# 2513_Replacement.net
KiCad netlist of a schematic drawn in EasyEDA
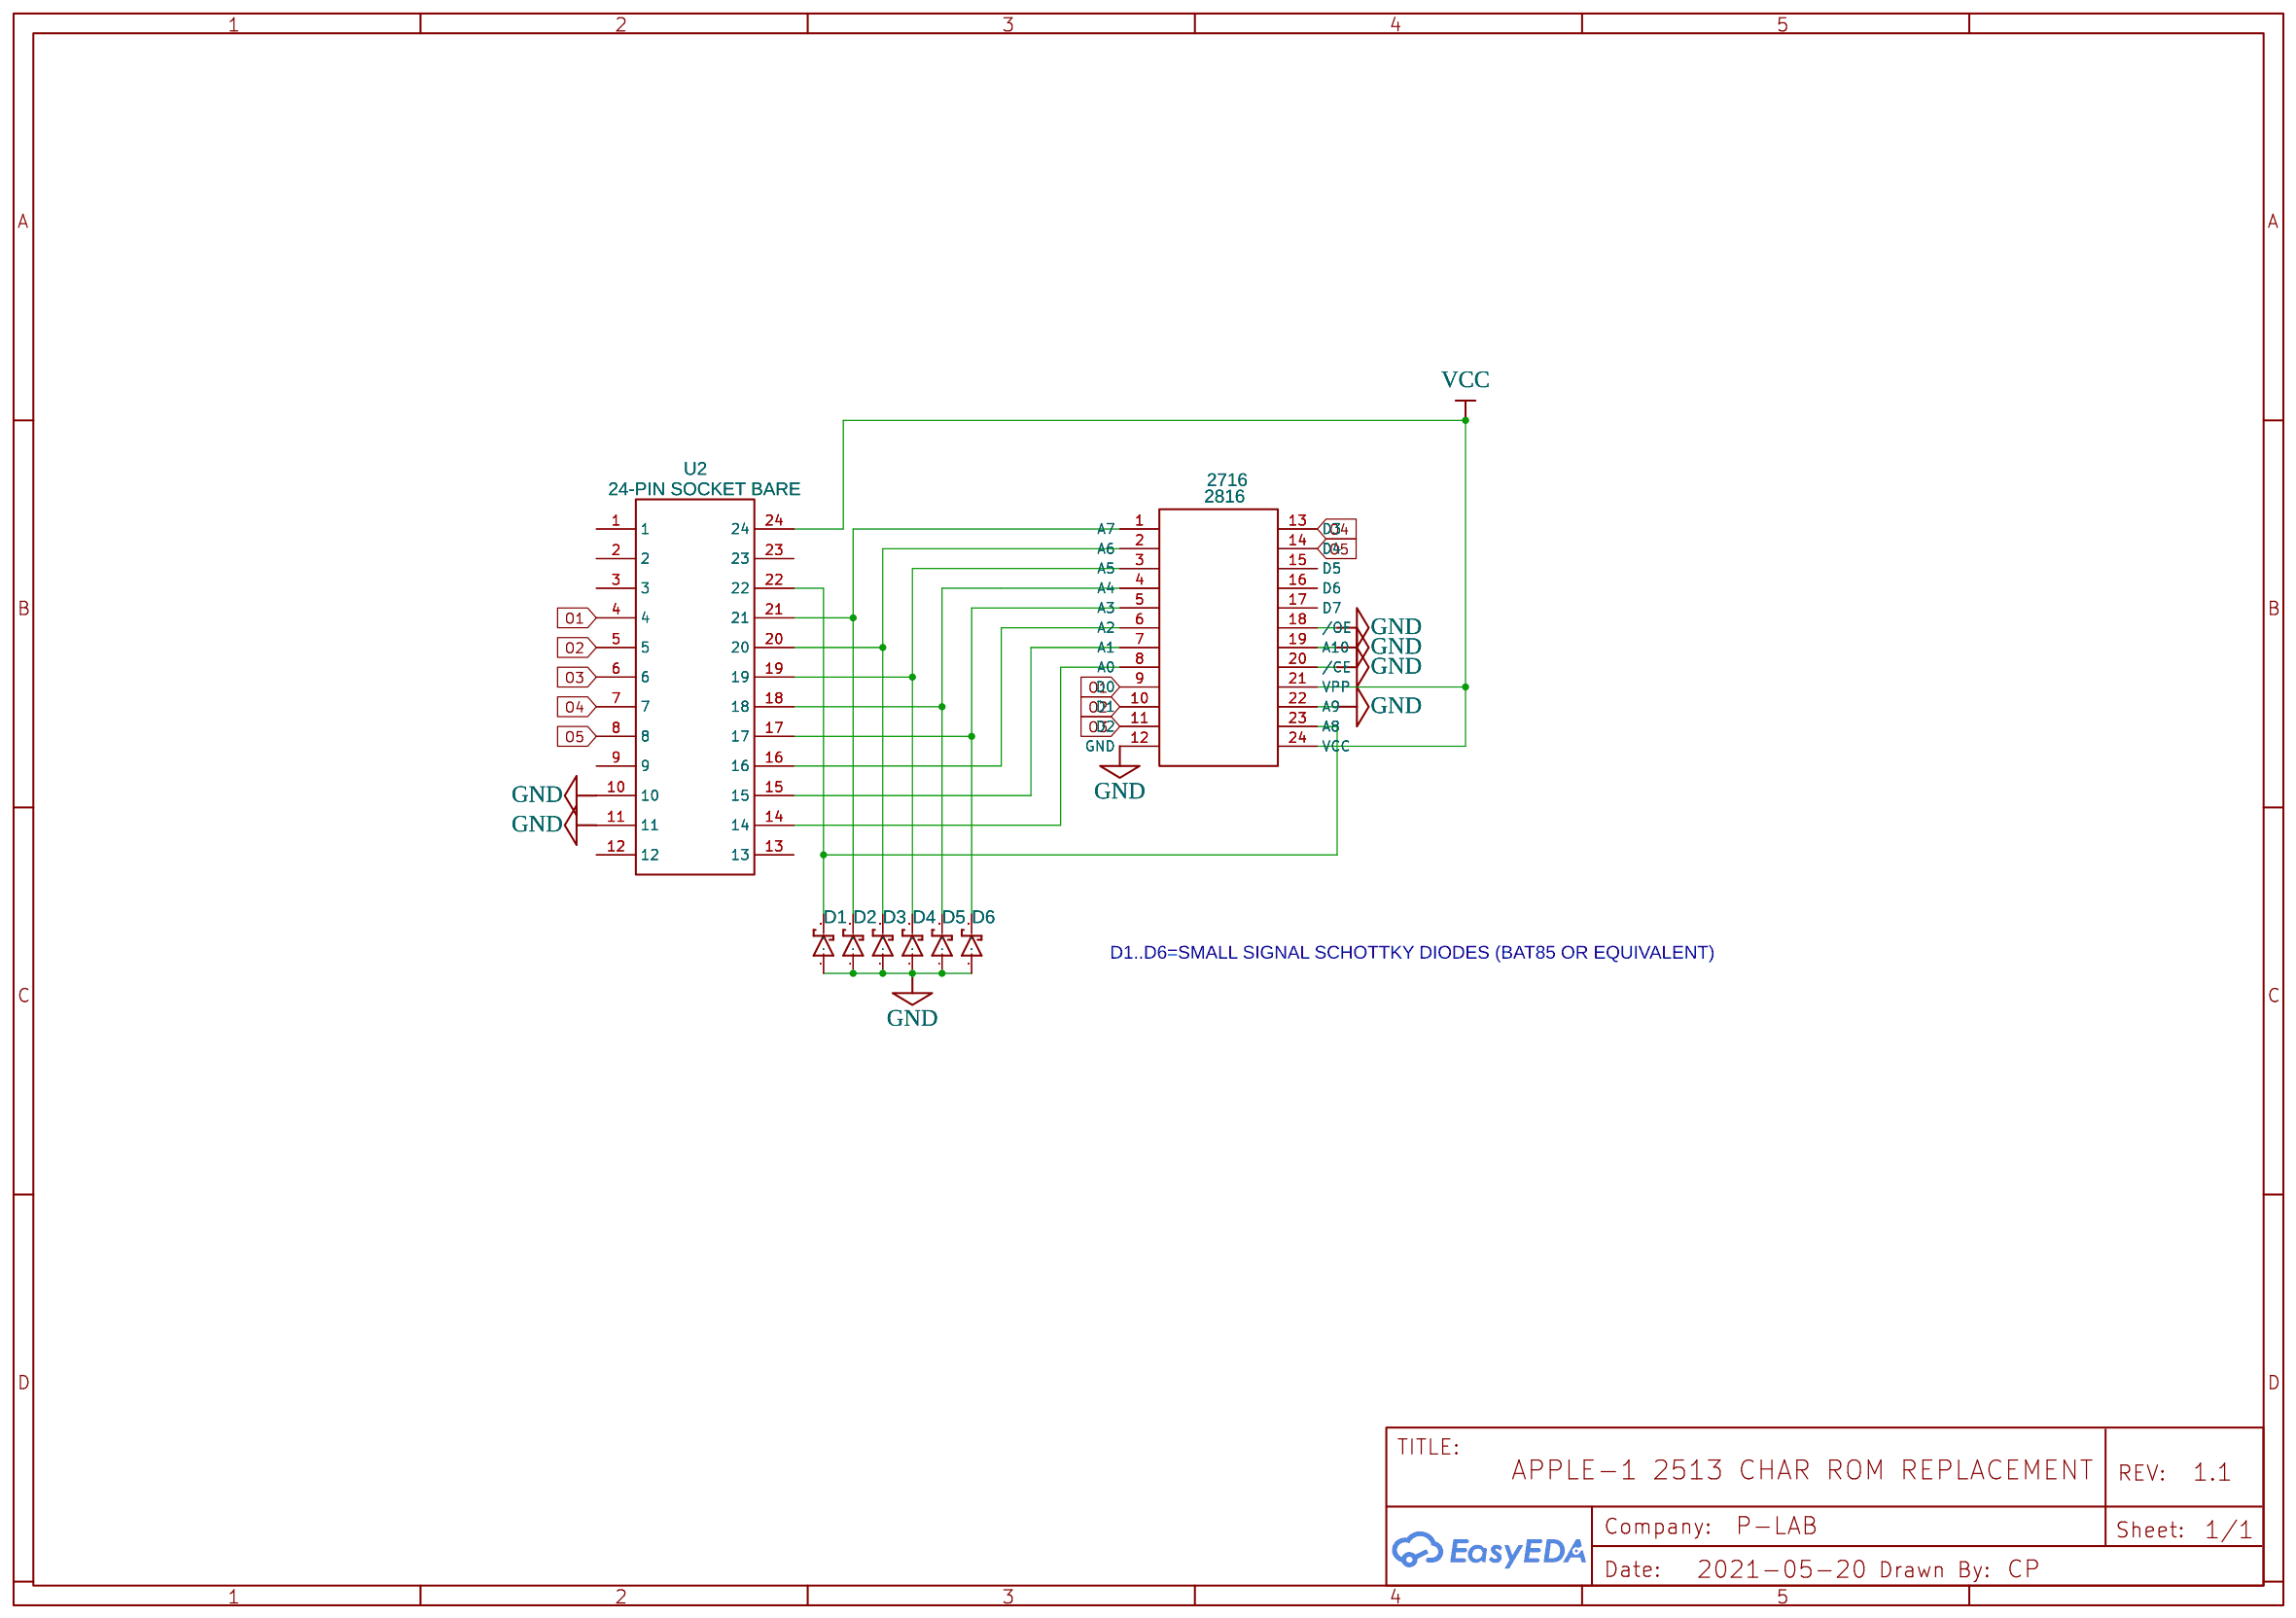
[diagram p0: schematic sheet]

(export (version "E")
  (design (tool "Eeschema 10.0.6"))
  (components
    (comp (ref "2716")
      (value "2816")
      (fields (field (name "BOM_Manufacturer Part") "27C16"))
      (libsource (lib "") (part "2716"))
    )
    (comp (ref "D1") (value "SCHOTTKY") (libsource (lib "") (part "SCHOTTKY")))
    (comp (ref "D2") (value "SCHOTTKY") (libsource (lib "") (part "SCHOTTKY")))
    (comp (ref "D3") (value "SCHOTTKY") (libsource (lib "") (part "SCHOTTKY")))
    (comp (ref "D4") (value "SCHOTTKY") (libsource (lib "") (part "SCHOTTKY")))
    (comp (ref "D5") (value "SCHOTTKY") (libsource (lib "") (part "SCHOTTKY")))
    (comp (ref "D6") (value "SCHOTTKY") (libsource (lib "") (part "SCHOTTKY")))
    (comp (ref "U2") (value "24-PIN SOCKET BARE") (libsource (lib "") (part "24-PIN SOCKET BARE")))
  )
  (nets
    (net (code "1") (name "GND") (class "Default")
      (node (ref "2716") (pin "12") (pinfunction "GND_12") (pintype "unspecified"))
      (node (ref "2716") (pin "18") (pinfunction "/OE_18") (pintype "unspecified"))
      (node (ref "2716") (pin "19") (pinfunction "A10_19") (pintype "unspecified"))
      (node (ref "2716") (pin "20") (pinfunction "/CE_20") (pintype "unspecified"))
      (node (ref "2716") (pin "22") (pinfunction "A9_22") (pintype "unspecified"))
      (node (ref "D1") (pin "A") (pinfunction "A_A") (pintype "bidirectional"))
      (node (ref "D2") (pin "A") (pinfunction "A_A") (pintype "bidirectional"))
      (node (ref "D3") (pin "A") (pinfunction "A_A") (pintype "bidirectional"))
      (node (ref "D4") (pin "A") (pinfunction "A_A") (pintype "bidirectional"))
      (node (ref "D5") (pin "A") (pinfunction "A_A") (pintype "bidirectional"))
      (node (ref "D6") (pin "A") (pinfunction "A_A") (pintype "bidirectional"))
      (node (ref "U2") (pin "10") (pinfunction "10_10") (pintype "unspecified"))
      (node (ref "U2") (pin "11") (pinfunction "11_11") (pintype "unspecified"))
    )
    (net (code "2") (name "Net-(2716-A0)") (class "Default")
      (node (ref "2716") (pin "8") (pinfunction "A0_8") (pintype "unspecified"))
      (node (ref "U2") (pin "14") (pinfunction "14_14") (pintype "unspecified"))
    )
    (net (code "3") (name "Net-(2716-A1)") (class "Default")
      (node (ref "2716") (pin "7") (pinfunction "A1_7") (pintype "unspecified"))
      (node (ref "U2") (pin "15") (pinfunction "15_15") (pintype "unspecified"))
    )
    (net (code "4") (name "Net-(2716-A2)") (class "Default")
      (node (ref "2716") (pin "6") (pinfunction "A2_6") (pintype "unspecified"))
      (node (ref "U2") (pin "16") (pinfunction "16_16") (pintype "unspecified"))
    )
    (net (code "5") (name "Net-(2716-A3)") (class "Default")
      (node (ref "2716") (pin "5") (pinfunction "A3_5") (pintype "unspecified"))
      (node (ref "D6") (pin "C") (pinfunction "C_C") (pintype "bidirectional"))
      (node (ref "U2") (pin "17") (pinfunction "17_17") (pintype "unspecified"))
    )
    (net (code "6") (name "Net-(2716-A4)") (class "Default")
      (node (ref "2716") (pin "4") (pinfunction "A4_4") (pintype "unspecified"))
      (node (ref "D5") (pin "C") (pinfunction "C_C") (pintype "bidirectional"))
      (node (ref "U2") (pin "18") (pinfunction "18_18") (pintype "bidirectional"))
    )
    (net (code "7") (name "Net-(2716-A5)") (class "Default")
      (node (ref "2716") (pin "3") (pinfunction "A5_3") (pintype "unspecified"))
      (node (ref "D4") (pin "C") (pinfunction "C_C") (pintype "bidirectional"))
      (node (ref "U2") (pin "19") (pinfunction "19_19") (pintype "bidirectional"))
    )
    (net (code "8") (name "Net-(2716-A6)") (class "Default")
      (node (ref "2716") (pin "2") (pinfunction "A6_2") (pintype "unspecified"))
      (node (ref "D3") (pin "C") (pinfunction "C_C") (pintype "bidirectional"))
      (node (ref "U2") (pin "20") (pinfunction "20_20") (pintype "bidirectional"))
    )
    (net (code "9") (name "Net-(2716-A7)") (class "Default")
      (node (ref "2716") (pin "1") (pinfunction "A7_1") (pintype "unspecified"))
      (node (ref "D2") (pin "C") (pinfunction "C_C") (pintype "bidirectional"))
      (node (ref "U2") (pin "21") (pinfunction "21_21") (pintype "bidirectional"))
    )
    (net (code "10") (name "Net-(2716-A8)") (class "Default")
      (node (ref "2716") (pin "23") (pinfunction "A8_23") (pintype "unspecified"))
      (node (ref "D1") (pin "C") (pinfunction "C_C") (pintype "bidirectional"))
      (node (ref "U2") (pin "22") (pinfunction "22_22") (pintype "bidirectional"))
    )
    (net (code "11") (name "O1") (class "Default")
      (node (ref "U2") (pin "4") (pinfunction "4_4") (pintype "unspecified"))
    )
    (net (code "12") (name "O2") (class "Default")
      (node (ref "2716") (pin "10") (pinfunction "D1_10") (pintype "unspecified"))
      (node (ref "U2") (pin "5") (pinfunction "5_5") (pintype "unspecified"))
    )
    (net (code "13") (name "O3") (class "Default")
      (node (ref "2716") (pin "11") (pinfunction "D2_11") (pintype "unspecified"))
      (node (ref "U2") (pin "6") (pinfunction "6_6") (pintype "unspecified"))
    )
    (net (code "14") (name "O4") (class "Default")
      (node (ref "2716") (pin "13") (pinfunction "D3_13") (pintype "unspecified"))
      (node (ref "U2") (pin "7") (pinfunction "7_7") (pintype "unspecified"))
    )
    (net (code "15") (name "O5") (class "Default")
      (node (ref "2716") (pin "14") (pinfunction "D4_14") (pintype "unspecified"))
      (node (ref "U2") (pin "8") (pinfunction "8_8") (pintype "unspecified"))
    )
    (net (code "16") (name "VCC") (class "Default")
      (node (ref "2716") (pin "21") (pinfunction "VPP_21") (pintype "unspecified"))
      (node (ref "2716") (pin "24") (pinfunction "VCC_24") (pintype "unspecified"))
      (node (ref "U2") (pin "24") (pinfunction "24_24") (pintype "passive"))
    )
    (net (code "17") (name "unconnected-(2716-D0-Pad9)") (class "Default")
      (node (ref "2716") (pin "9") (pinfunction "D0_9") (pintype "unspecified"))
    )
    (net (code "18") (name "unconnected-(2716-D5-Pad15)") (class "Default")
      (node (ref "2716") (pin "15") (pinfunction "D5_15") (pintype "unspecified"))
    )
    (net (code "19") (name "unconnected-(2716-D6-Pad16)") (class "Default")
      (node (ref "2716") (pin "16") (pinfunction "D6_16") (pintype "unspecified"))
    )
    (net (code "20") (name "unconnected-(2716-D7-Pad17)") (class "Default")
      (node (ref "2716") (pin "17") (pinfunction "D7_17") (pintype "unspecified"))
    )
    (net (code "21") (name "unconnected-(U2-Pad1)") (class "Default")
      (node (ref "U2") (pin "1") (pinfunction "1_1") (pintype "unspecified"))
    )
    (net (code "22") (name "unconnected-(U2-Pad2)") (class "Default")
      (node (ref "U2") (pin "2") (pinfunction "2_2") (pintype "unspecified"))
    )
    (net (code "23") (name "unconnected-(U2-Pad3)") (class "Default")
      (node (ref "U2") (pin "3") (pinfunction "3_3") (pintype "unspecified"))
    )
    (net (code "24") (name "unconnected-(U2-Pad9)") (class "Default")
      (node (ref "U2") (pin "9") (pinfunction "9_9") (pintype "unspecified"))
    )
    (net (code "25") (name "unconnected-(U2-Pad12)") (class "Default")
      (node (ref "U2") (pin "12") (pinfunction "12_12") (pintype "passive"))
    )
    (net (code "26") (name "unconnected-(U2-Pad13)") (class "Default")
      (node (ref "U2") (pin "13") (pinfunction "13_13") (pintype "unspecified"))
    )
    (net (code "27") (name "unconnected-(U2-Pad23)") (class "Default")
      (node (ref "U2") (pin "23") (pinfunction "23_23") (pintype "bidirectional"))
    )
  )
)
